# FIT_TCM_LDO.net
KiCad netlist of a schematic drawn in Altium Designer
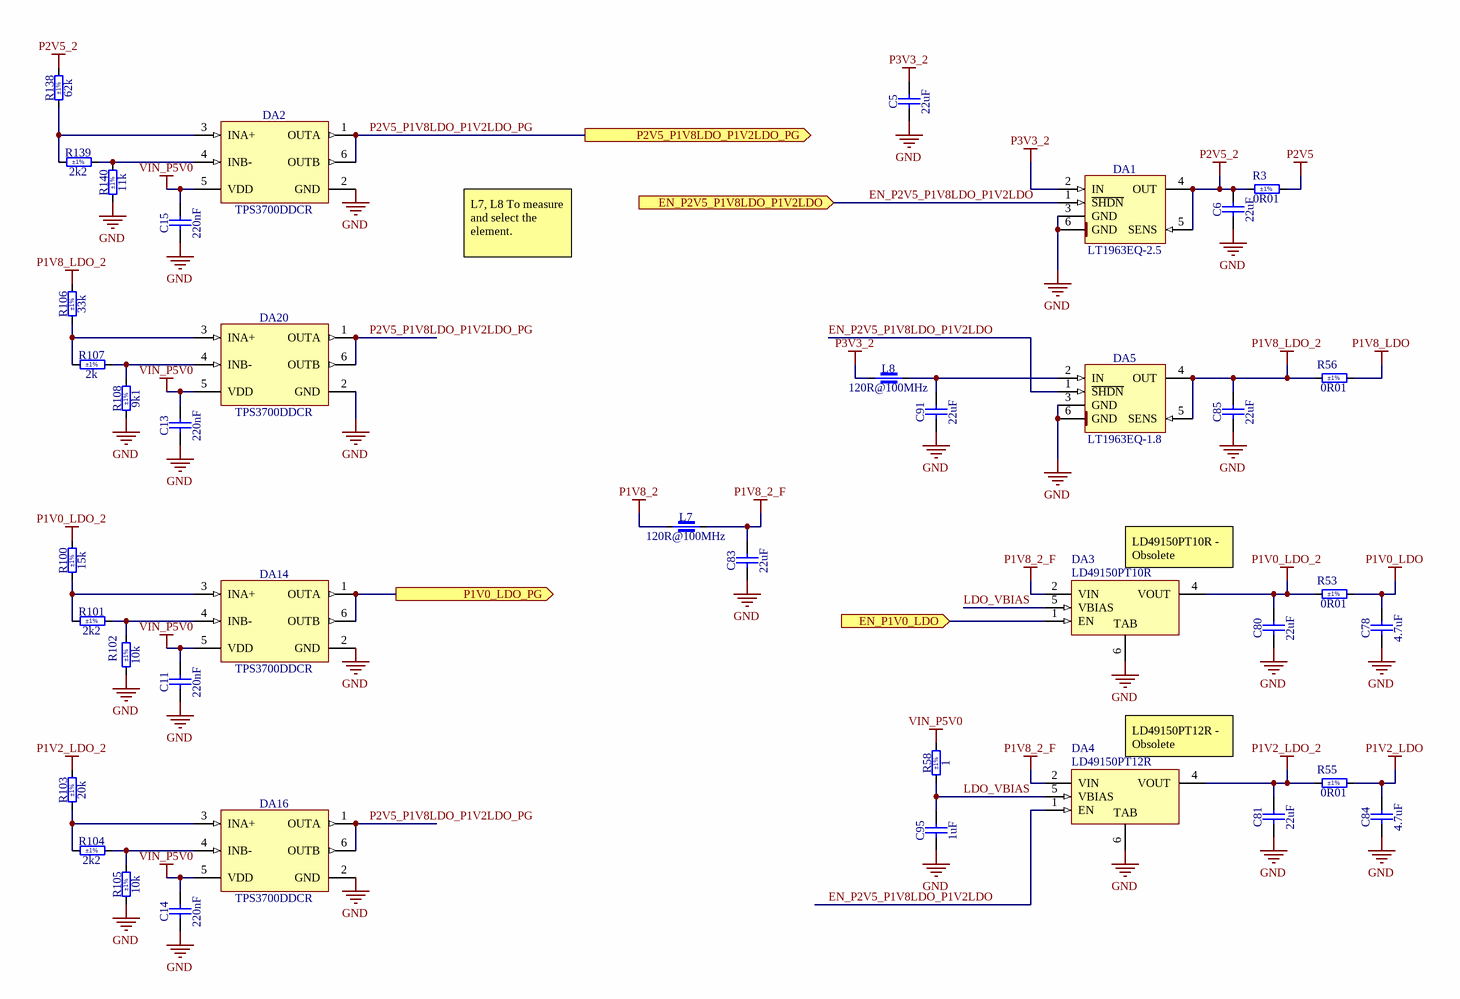
[diagram p0: FIT_TCM_LDO.SchDoc]

(export (version "E")
  (design (tool "Eeschema 10.0.6"))
  (components
    (comp (ref "C5")
      (value "22uF")
      (footprint "CAPC3216X180N")
      (description "Non-polarised capacitor")
      (fields
        (field (name "PART NUMBER") "CC1206_22UF_25V_20%_X5R")
        (field (name "VOLTAGE") "25V")
        (field (name "AUTHOR") "CERN DEM WB")
      )
      (libsource (lib "Capacitors") (part "Capacitor - non polarized"))
    )
    (comp (ref "C6")
      (value "22uF")
      (footprint "CAPC3216X180N")
      (description "Non-polarised capacitor")
      (fields
        (field (name "PART NUMBER") "CC1206_22UF_25V_20%_X5R")
        (field (name "VOLTAGE") "25V")
        (field (name "AUTHOR") "CERN DEM WB")
      )
      (libsource (lib "Capacitors") (part "Capacitor - non polarized"))
    )
    (comp (ref "C11")
      (value "220nF")
      (footprint "CAPC2012X135N")
      (description "Non-polarised capacitor")
      (fields
        (field (name "PART NUMBER") "CC0805_220NF_50V_10%_X7R")
        (field (name "VOLTAGE") "50V")
        (field (name "AUTHOR") "CERN DEM JLC")
      )
      (libsource (lib "Capacitors") (part "Capacitor - non polarized"))
    )
    (comp (ref "C13")
      (value "220nF")
      (footprint "CAPC2012X135N")
      (description "Non-polarised capacitor")
      (fields
        (field (name "PART NUMBER") "CC0805_220NF_50V_10%_X7R")
        (field (name "VOLTAGE") "50V")
        (field (name "AUTHOR") "CERN DEM JLC")
      )
      (libsource (lib "Capacitors") (part "Capacitor - non polarized"))
    )
    (comp (ref "C14")
      (value "220nF")
      (footprint "CAPC2012X135N")
      (description "Non-polarised capacitor")
      (fields
        (field (name "PART NUMBER") "CC0805_220NF_50V_10%_X7R")
        (field (name "VOLTAGE") "50V")
        (field (name "AUTHOR") "CERN DEM JLC")
      )
      (libsource (lib "Capacitors") (part "Capacitor - non polarized"))
    )
    (comp (ref "C15")
      (value "220nF")
      (footprint "CAPC2012X135N")
      (description "Non-polarised capacitor")
      (fields
        (field (name "PART NUMBER") "CC0805_220NF_50V_10%_X7R")
        (field (name "VOLTAGE") "50V")
        (field (name "AUTHOR") "CERN DEM JLC")
      )
      (libsource (lib "Capacitors") (part "Capacitor - non polarized"))
    )
    (comp (ref "C78")
      (value "4.7uF")
      (footprint "CAPC2012X145N")
      (description "Non-polarised capacitor")
      (fields
        (field (name "PART NUMBER") "CC0805_4.7UF_50V_10%_X7R")
        (field (name "VOLTAGE") "50V")
        (field (name "AUTHOR") "CERN DEM JMW")
      )
      (libsource (lib "Capacitors") (part "Capacitor - non polarized"))
    )
    (comp (ref "C80")
      (value "22uF")
      (footprint "CAPC3216X180N")
      (description "Non-polarised capacitor")
      (fields
        (field (name "PART NUMBER") "CC1206_22UF_25V_20%_X5R")
        (field (name "VOLTAGE") "25V")
        (field (name "AUTHOR") "CERN DEM WB")
      )
      (libsource (lib "Capacitors") (part "Capacitor - non polarized"))
    )
    (comp (ref "C81")
      (value "22uF")
      (footprint "CAPC3216X180N")
      (description "Non-polarised capacitor")
      (fields
        (field (name "PART NUMBER") "CC1206_22UF_25V_20%_X5R")
        (field (name "VOLTAGE") "25V")
        (field (name "AUTHOR") "CERN DEM WB")
      )
      (libsource (lib "Capacitors") (part "Capacitor - non polarized"))
    )
    (comp (ref "C83")
      (value "22uF")
      (footprint "CAPC3216X180N")
      (description "Non-polarised capacitor")
      (fields
        (field (name "PART NUMBER") "CC1206_22UF_25V_20%_X5R")
        (field (name "VOLTAGE") "25V")
        (field (name "AUTHOR") "CERN DEM WB")
      )
      (libsource (lib "Capacitors") (part "Capacitor - non polarized"))
    )
    (comp (ref "C84")
      (value "4.7uF")
      (footprint "CAPC2012X145N")
      (description "Non-polarised capacitor")
      (fields
        (field (name "PART NUMBER") "CC0805_4.7UF_50V_10%_X7R")
        (field (name "VOLTAGE") "50V")
        (field (name "AUTHOR") "CERN DEM JMW")
      )
      (libsource (lib "Capacitors") (part "Capacitor - non polarized"))
    )
    (comp (ref "C85")
      (value "22uF")
      (footprint "CAPC3216X180N")
      (description "Non-polarised capacitor")
      (fields
        (field (name "PART NUMBER") "CC1206_22UF_25V_20%_X5R")
        (field (name "VOLTAGE") "25V")
        (field (name "AUTHOR") "CERN DEM WB")
      )
      (libsource (lib "Capacitors") (part "Capacitor - non polarized"))
    )
    (comp (ref "C91")
      (value "22uF")
      (footprint "CAPC3216X180N")
      (description "Non-polarised capacitor")
      (fields
        (field (name "PART NUMBER") "CC1206_22UF_25V_20%_X5R")
        (field (name "VOLTAGE") "25V")
        (field (name "AUTHOR") "CERN DEM WB")
      )
      (libsource (lib "Capacitors") (part "Capacitor - non polarized"))
    )
    (comp (ref "C95")
      (value "1uF")
      (footprint "CAPC2012X140N")
      (description "Non-polarised capacitor")
      (fields
        (field (name "PART NUMBER") "CC0805_1UF_25V_10%_X7R")
        (field (name "VOLTAGE") "25V")
        (field (name "AUTHOR") "CERN DEM JLC")
      )
      (libsource (lib "Capacitors") (part "Capacitor - non polarized"))
    )
    (comp (ref "DA1")
      (value "LT1963EQ-2.5")
      (footprint "TO170P1394X457-6N-R900X1060")
      (description "1.5A, Fast Transient Response LDO Regulators")
      (fields (field (name "MANUFACTURER") "ANALOG DEVICES") (field (name "AUTHOR") "CERN DEM HF"))
      (libsource (lib "ICs And Semiconductors") (part "LT1963EQ-X"))
    )
    (comp (ref "DA2")
      (value "TPS3700DDCR")
      (footprint "SOT95P280X110-6N")
      (description "Window Comparator for Over- and Undervoltage Detection")
      (fields (field (name "MANUFACTURER") "TEXAS INSTRUMENTS") (field (name "AUTHOR") "CERN DEM JMW"))
      (libsource (lib "ICs And Semiconductors") (part "TPS3700DDC"))
    )
    (comp (ref "DA3")
      (value "LD49150PT10R")
      (footprint "PPAK_N")
      (description "1.5 Very Low Drop Voltage Regulator, 1.0V, 5-Pin PPAK, Tape and Reel")
      (libsource (lib "Altium Content Vault") (part "PM-REG-LD49300-SOT5"))
    )
    (comp (ref "DA4")
      (value "LD49150PT12R")
      (footprint "PPAK_M")
      (description "1.5 Very Low Drop Voltage Regulator, 1.2V, 5-Pin PPAK, Tape and Reel")
      (libsource (lib "Altium Content Vault") (part "PM-REG-LD49300-SOT5"))
    )
    (comp (ref "DA5")
      (value "LT1963EQ-1.8")
      (footprint "TO170P1394X457-6N-R900X1060")
      (description "1.5A, Fast Transient Response LDO Regulators")
      (fields (field (name "MANUFACTURER") "ANALOG DEVICES") (field (name "AUTHOR") "CERN DEM HF"))
      (libsource (lib "ICs And Semiconductors") (part "LT1963EQ-X"))
    )
    (comp (ref "DA14")
      (value "TPS3700DDCR")
      (footprint "SOT95P280X110-6N")
      (description "Window Comparator for Over- and Undervoltage Detection")
      (fields (field (name "MANUFACTURER") "TEXAS INSTRUMENTS") (field (name "AUTHOR") "CERN DEM JMW"))
      (libsource (lib "ICs And Semiconductors") (part "TPS3700DDC"))
    )
    (comp (ref "DA16")
      (value "TPS3700DDCR")
      (footprint "SOT95P280X110-6N")
      (description "Window Comparator for Over- and Undervoltage Detection")
      (fields (field (name "MANUFACTURER") "TEXAS INSTRUMENTS") (field (name "AUTHOR") "CERN DEM JMW"))
      (libsource (lib "ICs And Semiconductors") (part "TPS3700DDC"))
    )
    (comp (ref "DA20")
      (value "TPS3700DDCR")
      (footprint "SOT95P280X110-6N")
      (description "Window Comparator for Over- and Undervoltage Detection")
      (fields (field (name "MANUFACTURER") "TEXAS INSTRUMENTS") (field (name "AUTHOR") "CERN DEM JMW"))
      (libsource (lib "ICs And Semiconductors") (part "TPS3700DDC"))
    )
    (comp (ref "L7")
      (value "120R@100MHz")
      (footprint "IND_MURATA_BLM31KN")
      (fields
        (field (name "PART NUMBER") "IND1206_MURATA_BLM31KN121SN1")
        (field (name "POWER") "6A")
        (field (name "TOLERANCE") "±25%")
        (field (name "AUTHOR") "CERN DEM HF")
      )
      (libsource (lib "Inductors & Transformers") (part "Ferrite Bead"))
    )
    (comp (ref "L8")
      (value "120R@100MHz")
      (footprint "IND_MURATA_BLM31KN")
      (fields
        (field (name "PART NUMBER") "IND1206_MURATA_BLM31KN121SN1")
        (field (name "POWER") "6A")
        (field (name "TOLERANCE") "±25%")
        (field (name "AUTHOR") "CERN DEM HF")
      )
      (libsource (lib "Inductors & Transformers") (part "Ferrite Bead"))
    )
    (comp (ref "R3")
      (value "0R01")
      (footprint "RESC3216X80N")
      (description "Resistor - 1%")
      (fields
        (field (name "TOLERANCE") "±1%")
        (field (name "PART NUMBER") "R1206_0R01_1%_1W_100PPM_TT_LRMAM1206")
        (field (name "POWER") "1W")
        (field (name "AUTHOR") "CERN DEM BC")
      )
      (libsource (lib "Resistors") (part "Resistor - 1%"))
    )
    (comp (ref "R53")
      (value "0R01")
      (footprint "RESC3216X80N")
      (description "Resistor - 1%")
      (fields
        (field (name "TOLERANCE") "±1%")
        (field (name "PART NUMBER") "R1206_0R01_1%_1W_100PPM_TT_LRMAM1206")
        (field (name "POWER") "1W")
        (field (name "AUTHOR") "CERN DEM BC")
      )
      (libsource (lib "Resistors") (part "Resistor - 1%"))
    )
    (comp (ref "R55")
      (value "0R01")
      (footprint "RESC3216X80N")
      (description "Resistor - 1%")
      (fields
        (field (name "TOLERANCE") "±1%")
        (field (name "PART NUMBER") "R1206_0R01_1%_1W_100PPM_TT_LRMAM1206")
        (field (name "POWER") "1W")
        (field (name "AUTHOR") "CERN DEM BC")
      )
      (libsource (lib "Resistors") (part "Resistor - 1%"))
    )
    (comp (ref "R56")
      (value "0R01")
      (footprint "RESC3216X80N")
      (description "Resistor - 1%")
      (fields
        (field (name "TOLERANCE") "±1%")
        (field (name "PART NUMBER") "R1206_0R01_1%_1W_100PPM_TT_LRMAM1206")
        (field (name "POWER") "1W")
        (field (name "AUTHOR") "CERN DEM BC")
      )
      (libsource (lib "Resistors") (part "Resistor - 1%"))
    )
    (comp (ref "R58")
      (value "1")
      (footprint "RESC2012X60N")
      (description "Resistor - 1%")
      (fields
        (field (name "TOLERANCE") "±1%")
        (field (name "PART NUMBER") "R0805_1R_1%_0.125W_100PPM")
        (field (name "POWER") "0.125W")
        (field (name "AUTHOR") "CERN DEM HF")
      )
      (libsource (lib "Resistors") (part "Resistor - 1%"))
    )
    (comp (ref "R100")
      (value "15k")
      (footprint "RESC2012X60N")
      (description "Resistor - 1%")
      (fields
        (field (name "TOLERANCE") "±1%")
        (field (name "PART NUMBER") "R0805_15K_1%_0.125W_100PPM")
        (field (name "POWER") "0.125W")
        (field (name "AUTHOR") "CERN DEM JLC")
      )
      (libsource (lib "Resistors") (part "Resistor - 1%"))
    )
    (comp (ref "R101")
      (value "2k2")
      (footprint "RESC2012X60N")
      (description "Resistor - 1%")
      (fields
        (field (name "TOLERANCE") "±1%")
        (field (name "PART NUMBER") "R0805_2K2_1%_0.125W_100PPM")
        (field (name "POWER") "0.125W")
        (field (name "AUTHOR") "CERN DEM JLC")
      )
      (libsource (lib "Resistors") (part "Resistor - 1%"))
    )
    (comp (ref "R102")
      (value "10k")
      (footprint "RESC2012X60N")
      (description "Resistor - 1%")
      (fields
        (field (name "TOLERANCE") "±1%")
        (field (name "PART NUMBER") "R0805_10K_1%_0.125W_100PPM")
        (field (name "POWER") "0.125W")
        (field (name "AUTHOR") "CERN DEM JLC")
      )
      (libsource (lib "Resistors") (part "Resistor - 1%"))
    )
    (comp (ref "R103")
      (value "20k")
      (footprint "RESC2012X60N")
      (description "Resistor - 1%")
      (fields
        (field (name "TOLERANCE") "±1%")
        (field (name "PART NUMBER") "R0805_20K_1%_0.125W_100PPM")
        (field (name "POWER") "0.125W")
        (field (name "AUTHOR") "CERN DEM JLC")
      )
      (libsource (lib "Resistors") (part "Resistor - 1%"))
    )
    (comp (ref "R104")
      (value "2k2")
      (footprint "RESC2012X60N")
      (description "Resistor - 1%")
      (fields
        (field (name "TOLERANCE") "±1%")
        (field (name "PART NUMBER") "R0805_2K2_1%_0.125W_100PPM")
        (field (name "POWER") "0.125W")
        (field (name "AUTHOR") "CERN DEM JLC")
      )
      (libsource (lib "Resistors") (part "Resistor - 1%"))
    )
    (comp (ref "R105")
      (value "10k")
      (footprint "RESC2012X60N")
      (description "Resistor - 1%")
      (fields
        (field (name "TOLERANCE") "±1%")
        (field (name "PART NUMBER") "R0805_10K_1%_0.125W_100PPM")
        (field (name "POWER") "0.125W")
        (field (name "AUTHOR") "CERN DEM JLC")
      )
      (libsource (lib "Resistors") (part "Resistor - 1%"))
    )
    (comp (ref "R106")
      (value "33k")
      (footprint "RESC2012X60N")
      (description "Resistor - 1%")
      (fields
        (field (name "TOLERANCE") "±1%")
        (field (name "PART NUMBER") "R0805_33K_1%_0.125W_100PPM")
        (field (name "POWER") "0.125W")
        (field (name "AUTHOR") "CERN DEM JLC")
      )
      (libsource (lib "Resistors") (part "Resistor - 1%"))
    )
    (comp (ref "R107")
      (value "2k")
      (footprint "RESC2012X60N")
      (description "Resistor - 1%")
      (fields
        (field (name "TOLERANCE") "±1%")
        (field (name "PART NUMBER") "R0805_2K_1%_0.125W_100PPM")
        (field (name "POWER") "0.125W")
        (field (name "AUTHOR") "CERN DEM JLC")
      )
      (libsource (lib "Resistors") (part "Resistor - 1%"))
    )
    (comp (ref "R108")
      (value "9k1")
      (footprint "RESC2012X60N")
      (description "Resistor - 1%")
      (fields
        (field (name "TOLERANCE") "±1%")
        (field (name "PART NUMBER") "R0805_9K1_1%_0.125W_100PPM")
        (field (name "POWER") "0.125W")
        (field (name "AUTHOR") "CERN DEM JLC")
      )
      (libsource (lib "Resistors") (part "Resistor - 1%"))
    )
    (comp (ref "R138")
      (value "62k")
      (footprint "RESC2012X60N")
      (description "Resistor - 1%")
      (fields
        (field (name "TOLERANCE") "±1%")
        (field (name "PART NUMBER") "R0805_62K_1%_0.125W_100PPM")
        (field (name "POWER") "0.125W")
        (field (name "AUTHOR") "CERN DEM JLC")
      )
      (libsource (lib "Resistors") (part "Resistor - 1%"))
    )
    (comp (ref "R139")
      (value "2k2")
      (footprint "RESC2012X60N")
      (description "Resistor - 1%")
      (fields
        (field (name "TOLERANCE") "±1%")
        (field (name "PART NUMBER") "R0805_2K2_1%_0.125W_100PPM")
        (field (name "POWER") "0.125W")
        (field (name "AUTHOR") "CERN DEM JLC")
      )
      (libsource (lib "Resistors") (part "Resistor - 1%"))
    )
    (comp (ref "R140")
      (value "11k")
      (footprint "RESC2012X60N")
      (description "Resistor - 1%")
      (fields
        (field (name "TOLERANCE") "±1%")
        (field (name "PART NUMBER") "R0805_11K_1%_0.125W_100PPM")
        (field (name "POWER") "0.125W")
        (field (name "AUTHOR") "CERN DEM JLC")
      )
      (libsource (lib "Resistors") (part "Resistor - 1%"))
    )
  )
  (nets
    (net (code "1") (name "/EN_P1V0_LDO") (class "Default")
      (node (ref "DA3") (pin "1") (pinfunction "EN_1") (pintype "input"))
    )
    (net (code "2") (name "/EN_P2V5_P1V8LDO_P1V2LDO") (class "Default")
      (node (ref "DA1") (pin "1") (pinfunction "~{SHDN}_1") (pintype "input"))
      (node (ref "DA4") (pin "1") (pinfunction "EN_1") (pintype "input"))
      (node (ref "DA5") (pin "1") (pinfunction "~{SHDN}_1") (pintype "input"))
    )
    (net (code "3") (name "/LDO_VBIAS") (class "Default")
      (node (ref "C95") (pin "2") (pinfunction "2_2") (pintype "passive"))
      (node (ref "DA3") (pin "5") (pinfunction "VBIAS_5") (pintype "input"))
      (node (ref "DA4") (pin "5") (pinfunction "VBIAS_5") (pintype "input"))
      (node (ref "R58") (pin "1") (pinfunction "1_1") (pintype "passive"))
    )
    (net (code "4") (name "/P1V0_LDO_PG") (class "Default")
      (node (ref "DA14") (pin "1") (pinfunction "OUTA_1") (pintype "output"))
      (node (ref "DA14") (pin "6") (pinfunction "OUTB_6") (pintype "output"))
    )
    (net (code "5") (name "/P2V5_P1V8LDO_P1V2LDO_PG") (class "Default")
      (node (ref "DA16") (pin "1") (pinfunction "OUTA_1") (pintype "output"))
      (node (ref "DA16") (pin "6") (pinfunction "OUTB_6") (pintype "output"))
      (node (ref "DA2") (pin "1") (pinfunction "OUTA_1") (pintype "output"))
      (node (ref "DA2") (pin "6") (pinfunction "OUTB_6") (pintype "output"))
      (node (ref "DA20") (pin "1") (pinfunction "OUTA_1") (pintype "output"))
      (node (ref "DA20") (pin "6") (pinfunction "OUTB_6") (pintype "output"))
    )
    (net (code "6") (name "GND") (class "Default")
      (node (ref "C11") (pin "1") (pinfunction "1_1") (pintype "passive"))
      (node (ref "C13") (pin "1") (pinfunction "1_1") (pintype "passive"))
      (node (ref "C14") (pin "1") (pinfunction "1_1") (pintype "passive"))
      (node (ref "C15") (pin "1") (pinfunction "1_1") (pintype "passive"))
      (node (ref "C5") (pin "1") (pinfunction "1_1") (pintype "passive"))
      (node (ref "C6") (pin "1") (pinfunction "1_1") (pintype "passive"))
      (node (ref "C78") (pin "1") (pinfunction "1_1") (pintype "passive"))
      (node (ref "C80") (pin "1") (pinfunction "1_1") (pintype "passive"))
      (node (ref "C81") (pin "1") (pinfunction "1_1") (pintype "passive"))
      (node (ref "C83") (pin "1") (pinfunction "1_1") (pintype "passive"))
      (node (ref "C84") (pin "1") (pinfunction "1_1") (pintype "passive"))
      (node (ref "C85") (pin "1") (pinfunction "1_1") (pintype "passive"))
      (node (ref "C91") (pin "1") (pinfunction "1_1") (pintype "passive"))
      (node (ref "C95") (pin "1") (pinfunction "1_1") (pintype "passive"))
      (node (ref "DA1") (pin "3") (pinfunction "GND_3") (pintype "power_in"))
      (node (ref "DA1") (pin "6") (pinfunction "GND_6") (pintype "power_in"))
      (node (ref "DA14") (pin "2") (pinfunction "GND_2") (pintype "power_in"))
      (node (ref "DA16") (pin "2") (pinfunction "GND_2") (pintype "power_in"))
      (node (ref "DA2") (pin "2") (pinfunction "GND_2") (pintype "power_in"))
      (node (ref "DA20") (pin "2") (pinfunction "GND_2") (pintype "power_in"))
      (node (ref "DA3") (pin "6") (pinfunction "TAB_6") (pintype "power_in"))
      (node (ref "DA4") (pin "6") (pinfunction "TAB_6") (pintype "power_in"))
      (node (ref "DA5") (pin "3") (pinfunction "GND_3") (pintype "power_in"))
      (node (ref "DA5") (pin "6") (pinfunction "GND_6") (pintype "power_in"))
      (node (ref "R102") (pin "1") (pinfunction "1_1") (pintype "passive"))
      (node (ref "R105") (pin "1") (pinfunction "1_1") (pintype "passive"))
      (node (ref "R108") (pin "1") (pinfunction "1_1") (pintype "passive"))
      (node (ref "R140") (pin "1") (pinfunction "1_1") (pintype "passive"))
    )
    (net (code "7") (name "Net-(DA2-INA+)") (class "Default")
      (node (ref "DA2") (pin "3") (pinfunction "INA+_3") (pintype "input"))
      (node (ref "R138") (pin "1") (pinfunction "1_1") (pintype "passive"))
      (node (ref "R139") (pin "1") (pinfunction "1_1") (pintype "passive"))
    )
    (net (code "8") (name "Net-(DA2-INB-)") (class "Default")
      (node (ref "DA2") (pin "4") (pinfunction "INB-_4") (pintype "input"))
      (node (ref "R139") (pin "2") (pinfunction "2_2") (pintype "passive"))
      (node (ref "R140") (pin "2") (pinfunction "2_2") (pintype "passive"))
    )
    (net (code "9") (name "Net-(DA5-IN)") (class "Default")
      (node (ref "C91") (pin "2") (pinfunction "2_2") (pintype "passive"))
      (node (ref "DA5") (pin "2") (pinfunction "IN_2") (pintype "input"))
      (node (ref "L8") (pin "2") (pinfunction "2_2") (pintype "passive"))
    )
    (net (code "10") (name "Net-(DA14-INA+)") (class "Default")
      (node (ref "DA14") (pin "3") (pinfunction "INA+_3") (pintype "input"))
      (node (ref "R100") (pin "1") (pinfunction "1_1") (pintype "passive"))
      (node (ref "R101") (pin "1") (pinfunction "1_1") (pintype "passive"))
    )
    (net (code "11") (name "Net-(DA14-INB-)") (class "Default")
      (node (ref "DA14") (pin "4") (pinfunction "INB-_4") (pintype "input"))
      (node (ref "R101") (pin "2") (pinfunction "2_2") (pintype "passive"))
      (node (ref "R102") (pin "2") (pinfunction "2_2") (pintype "passive"))
    )
    (net (code "12") (name "Net-(DA16-INA+)") (class "Default")
      (node (ref "DA16") (pin "3") (pinfunction "INA+_3") (pintype "input"))
      (node (ref "R103") (pin "1") (pinfunction "1_1") (pintype "passive"))
      (node (ref "R104") (pin "1") (pinfunction "1_1") (pintype "passive"))
    )
    (net (code "13") (name "Net-(DA16-INB-)") (class "Default")
      (node (ref "DA16") (pin "4") (pinfunction "INB-_4") (pintype "input"))
      (node (ref "R104") (pin "2") (pinfunction "2_2") (pintype "passive"))
      (node (ref "R105") (pin "2") (pinfunction "2_2") (pintype "passive"))
    )
    (net (code "14") (name "Net-(DA20-INA+)") (class "Default")
      (node (ref "DA20") (pin "3") (pinfunction "INA+_3") (pintype "input"))
      (node (ref "R106") (pin "1") (pinfunction "1_1") (pintype "passive"))
      (node (ref "R107") (pin "1") (pinfunction "1_1") (pintype "passive"))
    )
    (net (code "15") (name "Net-(DA20-INB-)") (class "Default")
      (node (ref "DA20") (pin "4") (pinfunction "INB-_4") (pintype "input"))
      (node (ref "R107") (pin "2") (pinfunction "2_2") (pintype "passive"))
      (node (ref "R108") (pin "2") (pinfunction "2_2") (pintype "passive"))
    )
    (net (code "16") (name "P1V0_LDO") (class "Default")
      (node (ref "C78") (pin "2") (pinfunction "2_2") (pintype "passive"))
      (node (ref "R53") (pin "2") (pinfunction "2_2") (pintype "passive"))
    )
    (net (code "17") (name "P1V0_LDO_2") (class "Default")
      (node (ref "C80") (pin "2") (pinfunction "2_2") (pintype "passive"))
      (node (ref "DA3") (pin "4") (pinfunction "VOUT_4") (pintype "power_in"))
      (node (ref "R100") (pin "2") (pinfunction "2_2") (pintype "passive"))
      (node (ref "R53") (pin "1") (pinfunction "1_1") (pintype "passive"))
    )
    (net (code "18") (name "P1V2_LDO") (class "Default")
      (node (ref "C84") (pin "2") (pinfunction "2_2") (pintype "passive"))
      (node (ref "R55") (pin "2") (pinfunction "2_2") (pintype "passive"))
    )
    (net (code "19") (name "P1V2_LDO_2") (class "Default")
      (node (ref "C81") (pin "2") (pinfunction "2_2") (pintype "passive"))
      (node (ref "DA4") (pin "4") (pinfunction "VOUT_4") (pintype "power_in"))
      (node (ref "R103") (pin "2") (pinfunction "2_2") (pintype "passive"))
      (node (ref "R55") (pin "1") (pinfunction "1_1") (pintype "passive"))
    )
    (net (code "20") (name "P1V8_2") (class "Default")
      (node (ref "L7") (pin "1") (pinfunction "1_1") (pintype "passive"))
    )
    (net (code "21") (name "P1V8_2_F") (class "Default")
      (node (ref "C83") (pin "2") (pinfunction "2_2") (pintype "passive"))
      (node (ref "DA3") (pin "2") (pinfunction "VIN_2") (pintype "power_in"))
      (node (ref "DA4") (pin "2") (pinfunction "VIN_2") (pintype "power_in"))
      (node (ref "L7") (pin "2") (pinfunction "2_2") (pintype "passive"))
    )
    (net (code "22") (name "P1V8_LDO") (class "Default")
      (node (ref "R56") (pin "2") (pinfunction "2_2") (pintype "passive"))
    )
    (net (code "23") (name "P1V8_LDO_2") (class "Default")
      (node (ref "C85") (pin "2") (pinfunction "2_2") (pintype "passive"))
      (node (ref "DA5") (pin "4") (pinfunction "OUT_4") (pintype "power_in"))
      (node (ref "DA5") (pin "5") (pinfunction "SENS_5") (pintype "input"))
      (node (ref "R106") (pin "2") (pinfunction "2_2") (pintype "passive"))
      (node (ref "R56") (pin "1") (pinfunction "1_1") (pintype "passive"))
    )
    (net (code "24") (name "P2V5") (class "Default")
      (node (ref "R3") (pin "2") (pinfunction "2_2") (pintype "passive"))
    )
    (net (code "25") (name "P2V5_2") (class "Default")
      (node (ref "C6") (pin "2") (pinfunction "2_2") (pintype "passive"))
      (node (ref "DA1") (pin "4") (pinfunction "OUT_4") (pintype "power_in"))
      (node (ref "DA1") (pin "5") (pinfunction "SENS_5") (pintype "input"))
      (node (ref "R138") (pin "2") (pinfunction "2_2") (pintype "passive"))
      (node (ref "R3") (pin "1") (pinfunction "1_1") (pintype "passive"))
    )
    (net (code "26") (name "P3V3_2") (class "Default")
      (node (ref "C5") (pin "2") (pinfunction "2_2") (pintype "passive"))
      (node (ref "DA1") (pin "2") (pinfunction "IN_2") (pintype "input"))
      (node (ref "L8") (pin "1") (pinfunction "1_1") (pintype "passive"))
    )
    (net (code "27") (name "VIN_P5V0") (class "Default")
      (node (ref "C11") (pin "2") (pinfunction "2_2") (pintype "passive"))
      (node (ref "C13") (pin "2") (pinfunction "2_2") (pintype "passive"))
      (node (ref "C14") (pin "2") (pinfunction "2_2") (pintype "passive"))
      (node (ref "C15") (pin "2") (pinfunction "2_2") (pintype "passive"))
      (node (ref "DA14") (pin "5") (pinfunction "VDD_5") (pintype "power_in"))
      (node (ref "DA16") (pin "5") (pinfunction "VDD_5") (pintype "power_in"))
      (node (ref "DA2") (pin "5") (pinfunction "VDD_5") (pintype "power_in"))
      (node (ref "DA20") (pin "5") (pinfunction "VDD_5") (pintype "power_in"))
      (node (ref "R58") (pin "2") (pinfunction "2_2") (pintype "passive"))
    )
  )
)
